# Gastroscopy-LED.net
KiCad netlist of a schematic drawn in Altium Designer
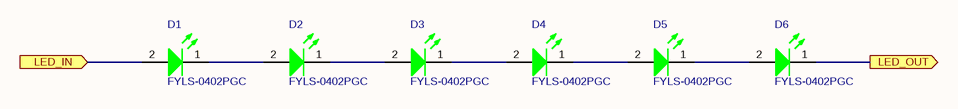
[diagram p0: Gastroscopy-LED.SchDoc]

(export (version "E")
  (design (tool "Eeschema 10.0.6"))
  (components
    (comp (ref "D1")
      (value "FYLS-0402PGC")
      (footprint "L_0402_GREEN")
      (description "LED GREEN CLEAR SMD")
      (libsource (lib "Gastroscopy-LED") (part "FYLS-0402PGC"))
    )
    (comp (ref "D2")
      (value "FYLS-0402PGC")
      (footprint "L_0402_GREEN")
      (description "LED GREEN CLEAR SMD")
      (libsource (lib "Gastroscopy-LED") (part "FYLS-0402PGC"))
    )
    (comp (ref "D3")
      (value "FYLS-0402PGC")
      (footprint "L_0402_GREEN")
      (description "LED GREEN CLEAR SMD")
      (libsource (lib "Gastroscopy-LED") (part "FYLS-0402PGC"))
    )
    (comp (ref "D4")
      (value "FYLS-0402PGC")
      (footprint "L_0402_GREEN")
      (description "LED GREEN CLEAR SMD")
      (libsource (lib "Gastroscopy-LED") (part "FYLS-0402PGC"))
    )
    (comp (ref "D5")
      (value "FYLS-0402PGC")
      (footprint "L_0402_GREEN")
      (description "LED GREEN CLEAR SMD")
      (libsource (lib "Gastroscopy-LED") (part "FYLS-0402PGC"))
    )
    (comp (ref "D6")
      (value "FYLS-0402PGC")
      (footprint "L_0402_GREEN")
      (description "LED GREEN CLEAR SMD")
      (libsource (lib "Gastroscopy-LED") (part "FYLS-0402PGC"))
    )
  )
  (nets
    (net (code "1") (name "/LED_IN") (class "Default")
      (node (ref "D1") (pin "2") (pinfunction "A_2") (pintype "passive"))
    )
    (net (code "2") (name "/LED_OUT") (class "Default")
      (node (ref "D6") (pin "1") (pinfunction "K_1") (pintype "passive"))
    )
    (net (code "3") (name "Net-(D1-K)") (class "Default")
      (node (ref "D1") (pin "1") (pinfunction "K_1") (pintype "passive"))
      (node (ref "D2") (pin "2") (pinfunction "A_2") (pintype "passive"))
    )
    (net (code "4") (name "Net-(D2-K)") (class "Default")
      (node (ref "D2") (pin "1") (pinfunction "K_1") (pintype "passive"))
      (node (ref "D3") (pin "2") (pinfunction "A_2") (pintype "passive"))
    )
    (net (code "5") (name "Net-(D3-K)") (class "Default")
      (node (ref "D3") (pin "1") (pinfunction "K_1") (pintype "passive"))
      (node (ref "D4") (pin "2") (pinfunction "A_2") (pintype "passive"))
    )
    (net (code "6") (name "Net-(D4-K)") (class "Default")
      (node (ref "D4") (pin "1") (pinfunction "K_1") (pintype "passive"))
      (node (ref "D5") (pin "2") (pinfunction "A_2") (pintype "passive"))
    )
    (net (code "7") (name "Net-(D5-K)") (class "Default")
      (node (ref "D5") (pin "1") (pinfunction "K_1") (pintype "passive"))
      (node (ref "D6") (pin "2") (pinfunction "A_2") (pintype "passive"))
    )
  )
)
